# motor_controller.net
KiCad netlist of a schematic drawn in Altium Designer
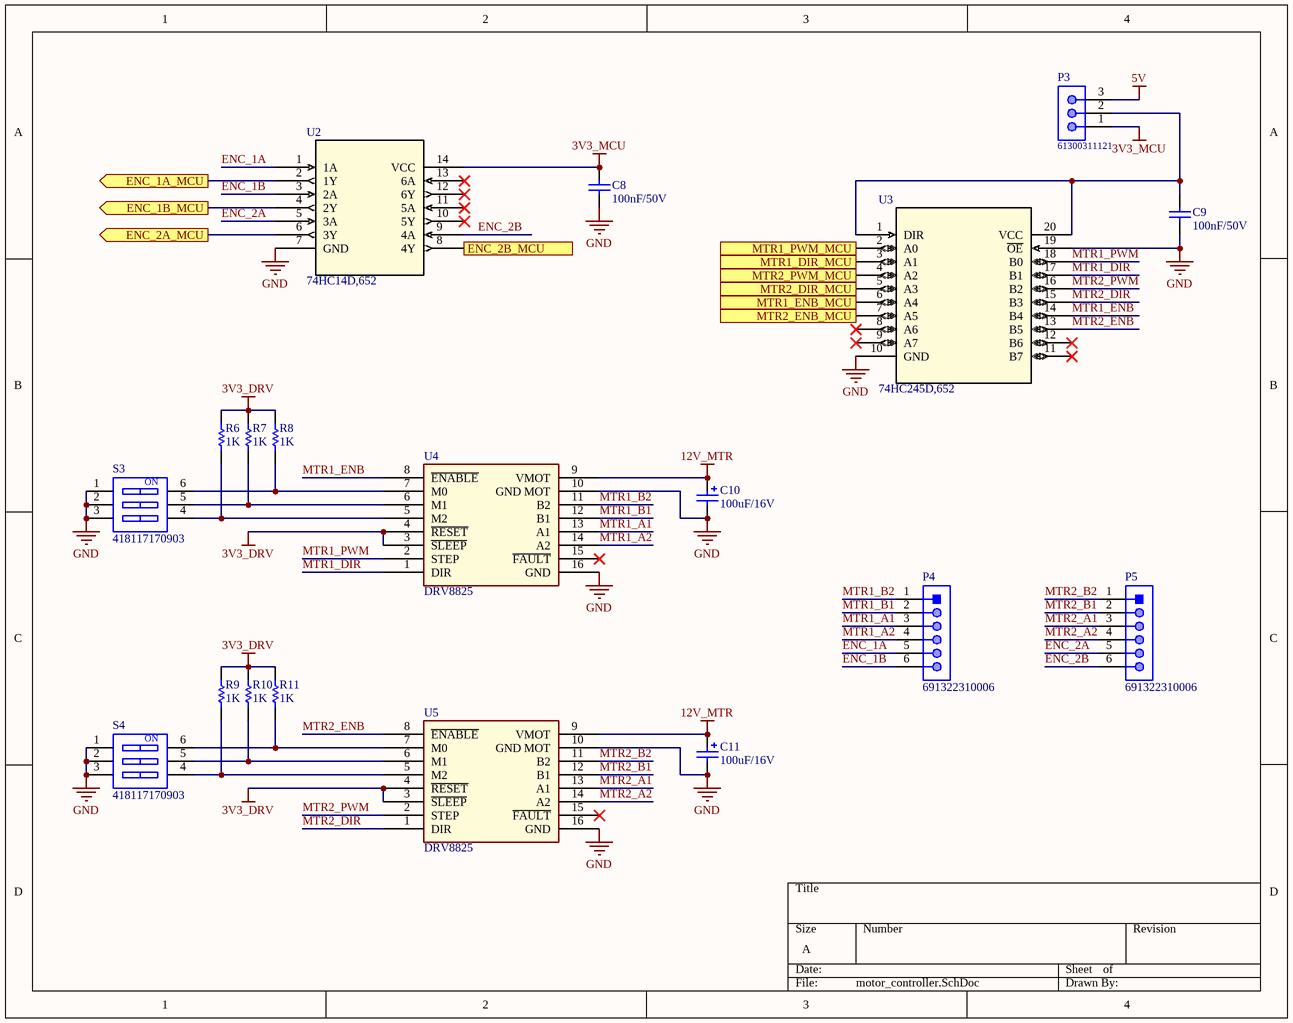
[diagram p0: motor_controller.SchDoc]

(export (version "E")
  (design (tool "Eeschema 10.0.6"))
  (components
    (comp (ref "C8")
      (value "100nF/50V")
      (footprint "CAP-SM-0805")
      (description "CAP CER 0.1UF 50V Y5V 0805")
      (fields
        (field (name "MANUFACTURER") "Samsung Electro-Mechanics")
        (field (name "MANUFACTURER PART NUMBER") "CL21F104ZBCNNNC")
      )
      (libsource (lib "Capacitor") (part "Cap-100nF-50V-0805"))
    )
    (comp (ref "C9")
      (value "100nF/50V")
      (footprint "CAP-SM-0805")
      (description "CAP CER 0.1UF 50V Y5V 0805")
      (fields
        (field (name "MANUFACTURER") "Samsung Electro-Mechanics")
        (field (name "MANUFACTURER PART NUMBER") "CL21F104ZBCNNNC")
      )
      (libsource (lib "Capacitor") (part "Cap-100nF-50V-0805"))
    )
    (comp (ref "C10")
      (value "100uF/16V")
      (footprint "CAP-SM-AL-SIZE-D-D6L6")
      (description "CAP ALUM 100UF 20% 16V SMD")
      (fields
        (field (name "MANUFACTURER") "Nichicon")
        (field (name "MANUFACTURER PART NUMBER") "UWX1C101MCL1GB")
      )
      (libsource (lib "Capacitor") (part "Cap-Al-100uF-16V-D6L5"))
    )
    (comp (ref "C11")
      (value "100uF/16V")
      (footprint "CAP-SM-AL-SIZE-D-D6L6")
      (description "CAP ALUM 100UF 20% 16V SMD")
      (fields
        (field (name "MANUFACTURER") "Nichicon")
        (field (name "MANUFACTURER PART NUMBER") "UWX1C101MCL1GB")
      )
      (libsource (lib "Capacitor") (part "Cap-Al-100uF-16V-D6L5"))
    )
    (comp (ref "P3")
      (value "61300311121")
      (footprint "61300311121")
      (description "WR-PHD Pin Header, THT, pitch 2.54mm, Single Row, Vertical, 3p")
      (fields (field (name "MANUFACTURER") "Wurth Elektronik"))
      (libsource (lib "Pluggable_Connector") (part "61300311121"))
    )
    (comp (ref "P4")
      (value "691322310006")
      (footprint "691322310006")
      (description "WR-TBL Serie 322 Horizontal PCB Header, Pluggable, pitch 3.81mm, 6p")
      (fields (field (name "PUBLISHER") "Wurth Elektronik"))
      (libsource (lib "Wire_Protector") (part "691322310006"))
    )
    (comp (ref "P5")
      (value "691322310006")
      (footprint "691322310006")
      (description "WR-TBL Serie 322 Horizontal PCB Header, Pluggable, pitch 3.81mm, 6p")
      (fields (field (name "PUBLISHER") "Wurth Elektronik"))
      (libsource (lib "Wire_Protector") (part "691322310006"))
    )
    (comp (ref "R6")
      (value "1K")
      (footprint "Resistor:RES-SM-0805")
      (description "RES 1K OHM 1% 1/4W 0805")
      (fields
        (field (name "MANUFACTURER") "Stackpole Electronics Inc")
        (field (name "MANUFACTURER PART NUMBER") "RNCP0805FTD1K00")
      )
      (libsource (lib "Resistor") (part "Res-1K-0805"))
    )
    (comp (ref "R7")
      (value "1K")
      (footprint "Resistor:RES-SM-0805")
      (description "RES 1K OHM 1% 1/4W 0805")
      (fields
        (field (name "MANUFACTURER") "Stackpole Electronics Inc")
        (field (name "MANUFACTURER PART NUMBER") "RNCP0805FTD1K00")
      )
      (libsource (lib "Resistor") (part "Res-1K-0805"))
    )
    (comp (ref "R8")
      (value "1K")
      (footprint "Resistor:RES-SM-0805")
      (description "RES 1K OHM 1% 1/4W 0805")
      (fields
        (field (name "MANUFACTURER") "Stackpole Electronics Inc")
        (field (name "MANUFACTURER PART NUMBER") "RNCP0805FTD1K00")
      )
      (libsource (lib "Resistor") (part "Res-1K-0805"))
    )
    (comp (ref "R9")
      (value "1K")
      (footprint "Resistor:RES-SM-0805")
      (description "RES 1K OHM 1% 1/4W 0805")
      (fields
        (field (name "MANUFACTURER") "Stackpole Electronics Inc")
        (field (name "MANUFACTURER PART NUMBER") "RNCP0805FTD1K00")
      )
      (libsource (lib "Resistor") (part "Res-1K-0805"))
    )
    (comp (ref "R10")
      (value "1K")
      (footprint "Resistor:RES-SM-0805")
      (description "RES 1K OHM 1% 1/4W 0805")
      (fields
        (field (name "MANUFACTURER") "Stackpole Electronics Inc")
        (field (name "MANUFACTURER PART NUMBER") "RNCP0805FTD1K00")
      )
      (libsource (lib "Resistor") (part "Res-1K-0805"))
    )
    (comp (ref "R11")
      (value "1K")
      (footprint "Resistor:RES-SM-0805")
      (description "RES 1K OHM 1% 1/4W 0805")
      (fields
        (field (name "MANUFACTURER") "Stackpole Electronics Inc")
        (field (name "MANUFACTURER PART NUMBER") "RNCP0805FTD1K00")
      )
      (libsource (lib "Resistor") (part "Res-1K-0805"))
    )
    (comp (ref "S3")
      (value "418117170903")
      (footprint "418117170903")
      (description "WS-DITV Compact THT Dip Switch, Flat Actuator, pitch 2.54mm, 3p")
      (fields (field (name "PUBLISHER") "Wurth Elektronik"))
      (libsource (lib "DIP_Switches") (part "418117170903"))
    )
    (comp (ref "S4")
      (value "418117170903")
      (footprint "418117170903")
      (description "WS-DITV Compact THT Dip Switch, Flat Actuator, pitch 2.54mm, 3p")
      (fields (field (name "PUBLISHER") "Wurth Elektronik"))
      (libsource (lib "DIP_Switches") (part "418117170903"))
    )
    (comp (ref "U2")
      (value "74HC14D,652")
      (footprint "74HC14D,652")
      (fields (field (name "COPYRIGHT") "Copyright (C) 2016 Accelerated Designs. All rights reserved"))
      (libsource (lib "IC") (part "74HC14D,652"))
    )
    (comp (ref "U3")
      (value "74HC245D,652")
      (footprint "74HC245D,652")
      (fields (field (name "COPYRIGHT") "Copyright (C) 2016 Accelerated Designs. All rights reserved"))
      (libsource (lib "IC") (part "74HC245D,652"))
    )
    (comp (ref "U4") (value "DRV8825") (footprint "DRV8825") (libsource (lib "Module") (part "DRV8825")))
    (comp (ref "U5") (value "DRV8825") (footprint "DRV8825") (libsource (lib "Module") (part "DRV8825")))
  )
  (nets
    (net (code "1") (name "/ENC_1A") (class "Default")
      (node (ref "P4") (pin "5") (pinfunction "5_5") (pintype "passive"))
      (node (ref "U2") (pin "1") (pinfunction "1A_1") (pintype "input"))
    )
    (net (code "2") (name "/ENC_1A_MCU") (class "Default")
      (node (ref "U2") (pin "2") (pinfunction "1Y_2") (pintype "output"))
    )
    (net (code "3") (name "/ENC_1B") (class "Default")
      (node (ref "P4") (pin "6") (pinfunction "6_6") (pintype "passive"))
      (node (ref "U2") (pin "3") (pinfunction "2A_3") (pintype "input"))
    )
    (net (code "4") (name "/ENC_1B_MCU") (class "Default")
      (node (ref "U2") (pin "4") (pinfunction "2Y_4") (pintype "output"))
    )
    (net (code "5") (name "/ENC_2A") (class "Default")
      (node (ref "P5") (pin "5") (pinfunction "5_5") (pintype "passive"))
      (node (ref "U2") (pin "5") (pinfunction "3A_5") (pintype "input"))
    )
    (net (code "6") (name "/ENC_2A_MCU") (class "Default")
      (node (ref "U2") (pin "6") (pinfunction "3Y_6") (pintype "output"))
    )
    (net (code "7") (name "/ENC_2B") (class "Default")
      (node (ref "P5") (pin "6") (pinfunction "6_6") (pintype "passive"))
      (node (ref "U2") (pin "9") (pinfunction "4A_9") (pintype "input"))
    )
    (net (code "8") (name "/ENC_2B_MCU") (class "Default")
      (node (ref "U2") (pin "8") (pinfunction "4Y_8") (pintype "output"))
    )
    (net (code "9") (name "/MTR1_A1") (class "Default")
      (node (ref "P4") (pin "3") (pinfunction "3_3") (pintype "passive"))
      (node (ref "U4") (pin "13") (pinfunction "A1_13") (pintype "passive"))
    )
    (net (code "10") (name "/MTR1_A2") (class "Default")
      (node (ref "P4") (pin "4") (pinfunction "4_4") (pintype "passive"))
      (node (ref "U4") (pin "14") (pinfunction "A2_14") (pintype "passive"))
    )
    (net (code "11") (name "/MTR1_B1") (class "Default")
      (node (ref "P4") (pin "2") (pinfunction "2_2") (pintype "passive"))
      (node (ref "U4") (pin "12") (pinfunction "B1_12") (pintype "passive"))
    )
    (net (code "12") (name "/MTR1_B2") (class "Default")
      (node (ref "P4") (pin "1") (pinfunction "1_1") (pintype "passive"))
      (node (ref "U4") (pin "11") (pinfunction "B2_11") (pintype "passive"))
    )
    (net (code "13") (name "/MTR1_DIR") (class "Default")
      (node (ref "U3") (pin "17") (pinfunction "B1_17") (pintype "bidirectional"))
      (node (ref "U4") (pin "1") (pinfunction "DIR_1") (pintype "passive"))
    )
    (net (code "14") (name "/MTR1_DIR_MCU") (class "Default")
      (node (ref "U3") (pin "3") (pinfunction "A1_3") (pintype "bidirectional"))
    )
    (net (code "15") (name "/MTR1_ENB") (class "Default")
      (node (ref "U3") (pin "14") (pinfunction "B4_14") (pintype "bidirectional"))
      (node (ref "U4") (pin "8") (pinfunction "~{ENABLE}_8") (pintype "passive"))
    )
    (net (code "16") (name "/MTR1_ENB_MCU") (class "Default")
      (node (ref "U3") (pin "6") (pinfunction "A4_6") (pintype "bidirectional"))
    )
    (net (code "17") (name "/MTR1_PWM") (class "Default")
      (node (ref "U3") (pin "18") (pinfunction "B0_18") (pintype "bidirectional"))
      (node (ref "U4") (pin "2") (pinfunction "STEP_2") (pintype "passive"))
    )
    (net (code "18") (name "/MTR1_PWM_MCU") (class "Default")
      (node (ref "U3") (pin "2") (pinfunction "A0_2") (pintype "bidirectional"))
    )
    (net (code "19") (name "/MTR2_A1") (class "Default")
      (node (ref "P5") (pin "3") (pinfunction "3_3") (pintype "passive"))
      (node (ref "U5") (pin "13") (pinfunction "A1_13") (pintype "passive"))
    )
    (net (code "20") (name "/MTR2_A2") (class "Default")
      (node (ref "P5") (pin "4") (pinfunction "4_4") (pintype "passive"))
      (node (ref "U5") (pin "14") (pinfunction "A2_14") (pintype "passive"))
    )
    (net (code "21") (name "/MTR2_B1") (class "Default")
      (node (ref "P5") (pin "2") (pinfunction "2_2") (pintype "passive"))
      (node (ref "U5") (pin "12") (pinfunction "B1_12") (pintype "passive"))
    )
    (net (code "22") (name "/MTR2_B2") (class "Default")
      (node (ref "P5") (pin "1") (pinfunction "1_1") (pintype "passive"))
      (node (ref "U5") (pin "11") (pinfunction "B2_11") (pintype "passive"))
    )
    (net (code "23") (name "/MTR2_DIR") (class "Default")
      (node (ref "U3") (pin "15") (pinfunction "B3_15") (pintype "bidirectional"))
      (node (ref "U5") (pin "1") (pinfunction "DIR_1") (pintype "passive"))
    )
    (net (code "24") (name "/MTR2_DIR_MCU") (class "Default")
      (node (ref "U3") (pin "5") (pinfunction "A3_5") (pintype "bidirectional"))
    )
    (net (code "25") (name "/MTR2_ENB") (class "Default")
      (node (ref "U3") (pin "13") (pinfunction "B5_13") (pintype "bidirectional"))
      (node (ref "U5") (pin "8") (pinfunction "~{ENABLE}_8") (pintype "passive"))
    )
    (net (code "26") (name "/MTR2_ENB_MCU") (class "Default")
      (node (ref "U3") (pin "7") (pinfunction "A5_7") (pintype "bidirectional"))
    )
    (net (code "27") (name "/MTR2_PWM") (class "Default")
      (node (ref "U3") (pin "16") (pinfunction "B2_16") (pintype "bidirectional"))
      (node (ref "U5") (pin "2") (pinfunction "STEP_2") (pintype "passive"))
    )
    (net (code "28") (name "/MTR2_PWM_MCU") (class "Default")
      (node (ref "U3") (pin "4") (pinfunction "A2_4") (pintype "bidirectional"))
    )
    (net (code "29") (name "3V3_DRV") (class "Default")
      (node (ref "R10") (pin "2") (pinfunction "2_2") (pintype "passive"))
      (node (ref "R11") (pin "2") (pinfunction "2_2") (pintype "passive"))
      (node (ref "R6") (pin "2") (pinfunction "2_2") (pintype "passive"))
      (node (ref "R7") (pin "2") (pinfunction "2_2") (pintype "passive"))
      (node (ref "R8") (pin "2") (pinfunction "2_2") (pintype "passive"))
      (node (ref "R9") (pin "2") (pinfunction "2_2") (pintype "passive"))
      (node (ref "U4") (pin "3") (pinfunction "~{SLEEP}_3") (pintype "passive"))
      (node (ref "U4") (pin "4") (pinfunction "~{RESET}_4") (pintype "passive"))
      (node (ref "U5") (pin "3") (pinfunction "~{SLEEP}_3") (pintype "passive"))
      (node (ref "U5") (pin "4") (pinfunction "~{RESET}_4") (pintype "passive"))
    )
    (net (code "30") (name "3V3_MCU") (class "Default")
      (node (ref "C8") (pin "2") (pinfunction "2_2") (pintype "passive"))
      (node (ref "P3") (pin "1") (pinfunction "1_1") (pintype "passive"))
      (node (ref "U2") (pin "14") (pinfunction "VCC_14") (pintype "power_in"))
    )
    (net (code "31") (name "5V") (class "Default")
      (node (ref "P3") (pin "3") (pinfunction "3_3") (pintype "passive"))
    )
    (net (code "32") (name "12V_MTR") (class "Default")
      (node (ref "C10") (pin "1") (pinfunction "1_1") (pintype "passive"))
      (node (ref "C11") (pin "1") (pinfunction "1_1") (pintype "passive"))
      (node (ref "U4") (pin "9") (pinfunction "VMOT_9") (pintype "passive"))
      (node (ref "U5") (pin "9") (pinfunction "VMOT_9") (pintype "passive"))
    )
    (net (code "33") (name "GND") (class "Default")
      (node (ref "C10") (pin "2") (pinfunction "2_2") (pintype "passive"))
      (node (ref "C11") (pin "2") (pinfunction "2_2") (pintype "passive"))
      (node (ref "C8") (pin "1") (pinfunction "1_1") (pintype "passive"))
      (node (ref "C9") (pin "1") (pinfunction "1_1") (pintype "passive"))
      (node (ref "S3") (pin "1") (pinfunction "1_1") (pintype "passive"))
      (node (ref "S3") (pin "2") (pinfunction "2_2") (pintype "passive"))
      (node (ref "S3") (pin "3") (pinfunction "3_3") (pintype "passive"))
      (node (ref "S4") (pin "1") (pinfunction "1_1") (pintype "passive"))
      (node (ref "S4") (pin "2") (pinfunction "2_2") (pintype "passive"))
      (node (ref "S4") (pin "3") (pinfunction "3_3") (pintype "passive"))
      (node (ref "U2") (pin "7") (pinfunction "GND_7") (pintype "power_in"))
      (node (ref "U3") (pin "10") (pinfunction "GND_10") (pintype "power_in"))
      (node (ref "U3") (pin "19") (pinfunction "~{OE}_19") (pintype "input"))
      (node (ref "U4") (pin "10") (pinfunction "GND_MOT_10") (pintype "passive"))
      (node (ref "U4") (pin "16") (pinfunction "GND_16") (pintype "passive"))
      (node (ref "U5") (pin "10") (pinfunction "GND_MOT_10") (pintype "passive"))
      (node (ref "U5") (pin "16") (pinfunction "GND_16") (pintype "passive"))
    )
    (net (code "34") (name "Net-(U3-DIR)") (class "Default")
      (node (ref "C9") (pin "2") (pinfunction "2_2") (pintype "passive"))
      (node (ref "P3") (pin "2") (pinfunction "2_2") (pintype "passive"))
      (node (ref "U3") (pin "1") (pinfunction "DIR_1") (pintype "input"))
      (node (ref "U3") (pin "20") (pinfunction "VCC_20") (pintype "power_in"))
    )
    (net (code "35") (name "Net-(U4-M0)") (class "Default")
      (node (ref "R8") (pin "1") (pinfunction "1_1") (pintype "passive"))
      (node (ref "S3") (pin "6") (pinfunction "6_6") (pintype "passive"))
      (node (ref "U4") (pin "7") (pinfunction "M0_7") (pintype "passive"))
    )
    (net (code "36") (name "Net-(U4-M1)") (class "Default")
      (node (ref "R7") (pin "1") (pinfunction "1_1") (pintype "passive"))
      (node (ref "S3") (pin "5") (pinfunction "5_5") (pintype "passive"))
      (node (ref "U4") (pin "6") (pinfunction "M1_6") (pintype "passive"))
    )
    (net (code "37") (name "Net-(U4-M2)") (class "Default")
      (node (ref "R6") (pin "1") (pinfunction "1_1") (pintype "passive"))
      (node (ref "S3") (pin "4") (pinfunction "4_4") (pintype "passive"))
      (node (ref "U4") (pin "5") (pinfunction "M2_5") (pintype "passive"))
    )
    (net (code "38") (name "Net-(U5-M0)") (class "Default")
      (node (ref "R11") (pin "1") (pinfunction "1_1") (pintype "passive"))
      (node (ref "S4") (pin "6") (pinfunction "6_6") (pintype "passive"))
      (node (ref "U5") (pin "7") (pinfunction "M0_7") (pintype "passive"))
    )
    (net (code "39") (name "Net-(U5-M1)") (class "Default")
      (node (ref "R10") (pin "1") (pinfunction "1_1") (pintype "passive"))
      (node (ref "S4") (pin "5") (pinfunction "5_5") (pintype "passive"))
      (node (ref "U5") (pin "6") (pinfunction "M1_6") (pintype "passive"))
    )
    (net (code "40") (name "Net-(U5-M2)") (class "Default")
      (node (ref "R9") (pin "1") (pinfunction "1_1") (pintype "passive"))
      (node (ref "S4") (pin "4") (pinfunction "4_4") (pintype "passive"))
      (node (ref "U5") (pin "5") (pinfunction "M2_5") (pintype "passive"))
    )
    (net (code "41") (name "unconnected-(U2-5A-Pad11)") (class "Default")
      (node (ref "U2") (pin "11") (pinfunction "5A_11") (pintype "input+no_connect"))
    )
    (net (code "42") (name "unconnected-(U2-5Y-Pad10)") (class "Default")
      (node (ref "U2") (pin "10") (pinfunction "5Y_10") (pintype "output+no_connect"))
    )
    (net (code "43") (name "unconnected-(U2-6A-Pad13)") (class "Default")
      (node (ref "U2") (pin "13") (pinfunction "6A_13") (pintype "input+no_connect"))
    )
    (net (code "44") (name "unconnected-(U2-6Y-Pad12)") (class "Default")
      (node (ref "U2") (pin "12") (pinfunction "6Y_12") (pintype "output+no_connect"))
    )
    (net (code "45") (name "unconnected-(U3-A6-Pad8)") (class "Default")
      (node (ref "U3") (pin "8") (pinfunction "A6_8") (pintype "bidirectional+no_connect"))
    )
    (net (code "46") (name "unconnected-(U3-A7-Pad9)") (class "Default")
      (node (ref "U3") (pin "9") (pinfunction "A7_9") (pintype "bidirectional+no_connect"))
    )
    (net (code "47") (name "unconnected-(U3-B6-Pad12)") (class "Default")
      (node (ref "U3") (pin "12") (pinfunction "B6_12") (pintype "bidirectional+no_connect"))
    )
    (net (code "48") (name "unconnected-(U3-B7-Pad11)") (class "Default")
      (node (ref "U3") (pin "11") (pinfunction "B7_11") (pintype "bidirectional+no_connect"))
    )
    (net (code "49") (name "unconnected-(U4-~{FAULT}-Pad15)") (class "Default")
      (node (ref "U4") (pin "15") (pinfunction "~{FAULT}_15") (pintype "passive+no_connect"))
    )
    (net (code "50") (name "unconnected-(U5-~{FAULT}-Pad15)") (class "Default")
      (node (ref "U5") (pin "15") (pinfunction "~{FAULT}_15") (pintype "passive+no_connect"))
    )
  )
)
